# ESP8266_ESP-01_Breakout_2015-11-16.net
KiCad netlist of a schematic drawn in EAGLE
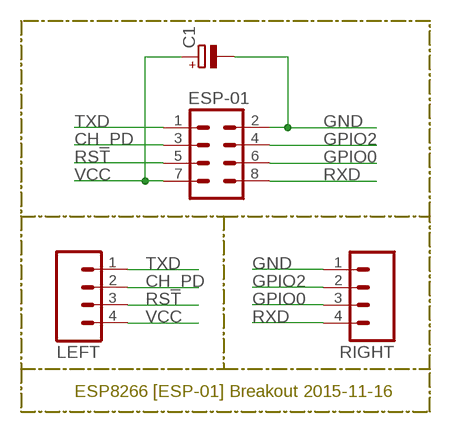
[diagram p0: schematic, sheet 1]

(export (version "E")
  (design (tool "Eeschema 10.0.6"))
  (components
    (comp (ref "C1")
      (value "CPOL-EUB45181B")
      (footprint "eagle-import:B45181B")
      (libsource (lib "eagle-import") (part "CPOL-EUB45181B"))
    )
    (comp (ref "ESP-01")
      (value "M04X2")
      (footprint "eagle-import:2X4")
      (libsource (lib "eagle-import") (part "M04X2"))
    )
    (comp (ref "LEFT")
      (value "M04LONGPADS")
      (footprint "eagle-import:1X04_LONGPADS")
      (libsource (lib "eagle-import") (part "M04LONGPADS"))
    )
    (comp (ref "RIGHT")
      (value "M04LONGPADS")
      (footprint "eagle-import:1X04_LONGPADS")
      (libsource (lib "eagle-import") (part "M04LONGPADS"))
    )
  )
  (nets
    (net (code "1") (name "/CH_PD") (class "Default")
      (node (ref "ESP-01") (pin "3") (pinfunction "3_3") (pintype "passive"))
      (node (ref "LEFT") (pin "2") (pinfunction "2_2") (pintype "passive"))
    )
    (net (code "2") (name "/GND") (class "Default")
      (node (ref "C1") (pin "-") (pinfunction "-_-") (pintype "passive"))
      (node (ref "ESP-01") (pin "2") (pinfunction "2_2") (pintype "passive"))
      (node (ref "RIGHT") (pin "1") (pinfunction "1_1") (pintype "passive"))
    )
    (net (code "3") (name "/GPIO0") (class "Default")
      (node (ref "ESP-01") (pin "6") (pinfunction "6_6") (pintype "passive"))
      (node (ref "RIGHT") (pin "3") (pinfunction "3_3") (pintype "passive"))
    )
    (net (code "4") (name "/GPIO2") (class "Default")
      (node (ref "ESP-01") (pin "4") (pinfunction "4_4") (pintype "passive"))
      (node (ref "RIGHT") (pin "2") (pinfunction "2_2") (pintype "passive"))
    )
    (net (code "5") (name "/RST") (class "Default")
      (node (ref "ESP-01") (pin "5") (pinfunction "5_5") (pintype "passive"))
      (node (ref "LEFT") (pin "3") (pinfunction "3_3") (pintype "passive"))
    )
    (net (code "6") (name "/RXD") (class "Default")
      (node (ref "ESP-01") (pin "8") (pinfunction "8_8") (pintype "passive"))
      (node (ref "RIGHT") (pin "4") (pinfunction "4_4") (pintype "passive"))
    )
    (net (code "7") (name "/TXD") (class "Default")
      (node (ref "ESP-01") (pin "1") (pinfunction "1_1") (pintype "passive"))
      (node (ref "LEFT") (pin "1") (pinfunction "1_1") (pintype "passive"))
    )
    (net (code "8") (name "/VCC") (class "Default")
      (node (ref "C1") (pin "+") (pinfunction "+_+") (pintype "passive"))
      (node (ref "ESP-01") (pin "7") (pinfunction "7_7") (pintype "passive"))
      (node (ref "LEFT") (pin "4") (pinfunction "4_4") (pintype "passive"))
    )
  )
)
